# d104-lofi-delay.net
KiCad netlist of a schematic drawn in EAGLE
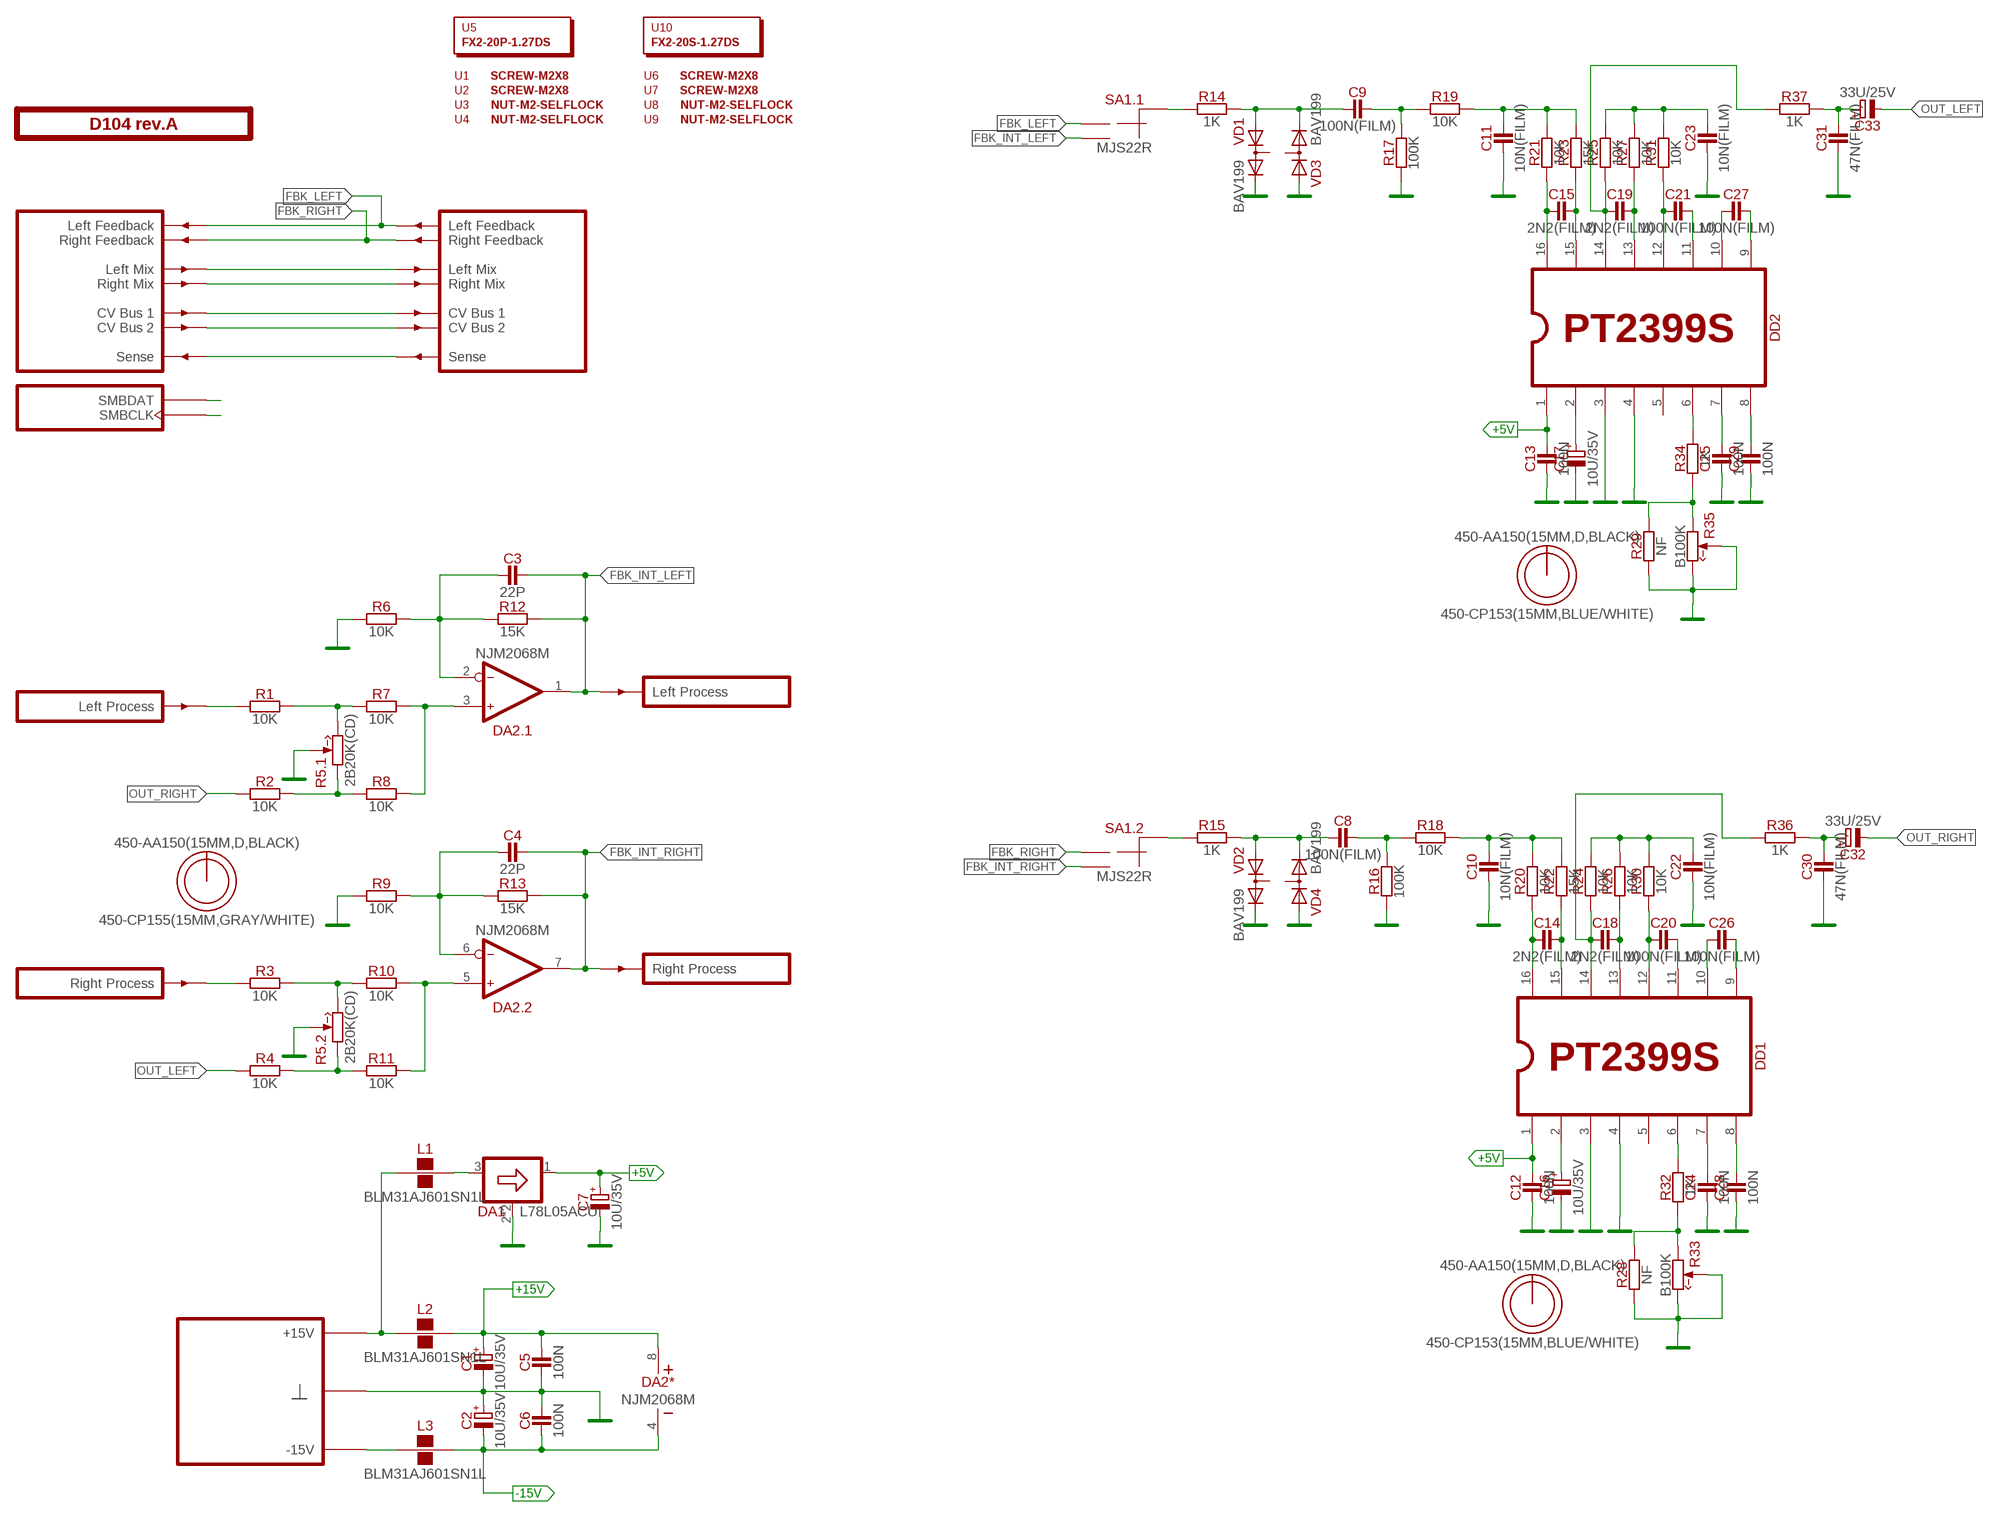
[diagram p0: schematic, sheet 1]

(export (version "E")
  (design (tool "Eeschema 10.0.6"))
  (components
    (comp (ref "C1")
      (value "10U/35V")
      (footprint "eagle-import:E2-5")
      (libsource (lib "eagle-import") (part "?10U/35V"))
    )
    (comp (ref "C2")
      (value "10U/35V")
      (footprint "eagle-import:E2-5")
      (libsource (lib "eagle-import") (part "?10U/35V"))
    )
    (comp (ref "C3")
      (value "22P")
      (footprint "eagle-import:C-0805")
      (libsource (lib "eagle-import") (part "?22P"))
    )
    (comp (ref "C4")
      (value "22P")
      (footprint "eagle-import:C-0805")
      (libsource (lib "eagle-import") (part "?22P"))
    )
    (comp (ref "C5")
      (value "100N")
      (footprint "eagle-import:C-0805")
      (libsource (lib "eagle-import") (part "?100N"))
    )
    (comp (ref "C6")
      (value "100N")
      (footprint "eagle-import:C-0805")
      (libsource (lib "eagle-import") (part "?100N"))
    )
    (comp (ref "C7")
      (value "10U/35V")
      (footprint "eagle-import:E2-5")
      (libsource (lib "eagle-import") (part "?10U/35V"))
    )
    (comp (ref "C8")
      (value "100N(FILM)")
      (footprint "eagle-import:C050-025X075")
      (libsource (lib "eagle-import") (part "?100N(FILM)"))
    )
    (comp (ref "C9")
      (value "100N(FILM)")
      (footprint "eagle-import:C050-025X075")
      (libsource (lib "eagle-import") (part "?100N(FILM)"))
    )
    (comp (ref "C10")
      (value "10N(FILM)")
      (footprint "eagle-import:C050-025X075")
      (libsource (lib "eagle-import") (part "?10N(FILM)"))
    )
    (comp (ref "C11")
      (value "10N(FILM)")
      (footprint "eagle-import:C050-025X075")
      (libsource (lib "eagle-import") (part "?10N(FILM)"))
    )
    (comp (ref "C12")
      (value "100N")
      (footprint "eagle-import:C-0805")
      (libsource (lib "eagle-import") (part "?100N"))
    )
    (comp (ref "C13")
      (value "100N")
      (footprint "eagle-import:C-0805")
      (libsource (lib "eagle-import") (part "?100N"))
    )
    (comp (ref "C14")
      (value "2N2(FILM)")
      (footprint "eagle-import:C050-025X075")
      (libsource (lib "eagle-import") (part "?2N2(FILM)"))
    )
    (comp (ref "C15")
      (value "2N2(FILM)")
      (footprint "eagle-import:C050-025X075")
      (libsource (lib "eagle-import") (part "?2N2(FILM)"))
    )
    (comp (ref "C16")
      (value "10U/35V")
      (footprint "eagle-import:E2-5")
      (libsource (lib "eagle-import") (part "?10U/35V"))
    )
    (comp (ref "C17")
      (value "10U/35V")
      (footprint "eagle-import:E2-5")
      (libsource (lib "eagle-import") (part "?10U/35V"))
    )
    (comp (ref "C18")
      (value "2N2(FILM)")
      (footprint "eagle-import:C050-025X075")
      (libsource (lib "eagle-import") (part "?2N2(FILM)"))
    )
    (comp (ref "C19")
      (value "2N2(FILM)")
      (footprint "eagle-import:C050-025X075")
      (libsource (lib "eagle-import") (part "?2N2(FILM)"))
    )
    (comp (ref "C20")
      (value "100N(FILM)")
      (footprint "eagle-import:C050-025X075")
      (libsource (lib "eagle-import") (part "?100N(FILM)"))
    )
    (comp (ref "C21")
      (value "100N(FILM)")
      (footprint "eagle-import:C050-025X075")
      (libsource (lib "eagle-import") (part "?100N(FILM)"))
    )
    (comp (ref "C22")
      (value "10N(FILM)")
      (footprint "eagle-import:C050-025X075")
      (libsource (lib "eagle-import") (part "?10N(FILM)"))
    )
    (comp (ref "C23")
      (value "10N(FILM)")
      (footprint "eagle-import:C050-025X075")
      (libsource (lib "eagle-import") (part "?10N(FILM)"))
    )
    (comp (ref "C24")
      (value "100N")
      (footprint "eagle-import:C-0805")
      (libsource (lib "eagle-import") (part "?100N"))
    )
    (comp (ref "C25")
      (value "100N")
      (footprint "eagle-import:C-0805")
      (libsource (lib "eagle-import") (part "?100N"))
    )
    (comp (ref "C26")
      (value "100N(FILM)")
      (footprint "eagle-import:C050-025X075")
      (libsource (lib "eagle-import") (part "?100N(FILM)"))
    )
    (comp (ref "C27")
      (value "100N(FILM)")
      (footprint "eagle-import:C050-025X075")
      (libsource (lib "eagle-import") (part "?100N(FILM)"))
    )
    (comp (ref "C28")
      (value "100N")
      (footprint "eagle-import:C-0805")
      (libsource (lib "eagle-import") (part "?100N"))
    )
    (comp (ref "C29")
      (value "100N")
      (footprint "eagle-import:C-0805")
      (libsource (lib "eagle-import") (part "?100N"))
    )
    (comp (ref "C30")
      (value "47N(FILM)")
      (footprint "eagle-import:C050-025X075")
      (libsource (lib "eagle-import") (part "?47N(FILM)"))
    )
    (comp (ref "C31")
      (value "47N(FILM)")
      (footprint "eagle-import:C050-025X075")
      (libsource (lib "eagle-import") (part "?47N(FILM)"))
    )
    (comp (ref "C32")
      (value "33U/25V")
      (footprint "eagle-import:E2,5-7")
      (libsource (lib "eagle-import") (part "?33U/25V"))
    )
    (comp (ref "C33")
      (value "33U/25V")
      (footprint "eagle-import:E2,5-7")
      (libsource (lib "eagle-import") (part "?33U/25V"))
    )
    (comp (ref "DA1")
      (value "L78L05ACU")
      (footprint "eagle-import:SOT89")
      (libsource (lib "eagle-import") (part "?L78L05ACU"))
    )
    (comp (ref "DA2")
      (value "NJM2068M")
      (footprint "eagle-import:SO-8")
      (libsource (lib "eagle-import") (part "NJM2068M"))
    )
    (comp (ref "DD1")
      (value "PT2399S")
      (footprint "eagle-import:SO-16")
      (libsource (lib "eagle-import") (part "PT2399S"))
    )
    (comp (ref "DD2")
      (value "PT2399S")
      (footprint "eagle-import:SO-16")
      (libsource (lib "eagle-import") (part "PT2399S"))
    )
    (comp (ref "L1")
      (value "BLM31AJ601SN1L")
      (footprint "eagle-import:1206")
      (libsource (lib "eagle-import") (part "BLM31AJ601SN1L"))
    )
    (comp (ref "L2")
      (value "BLM31AJ601SN1L")
      (footprint "eagle-import:1206")
      (libsource (lib "eagle-import") (part "BLM31AJ601SN1L"))
    )
    (comp (ref "L3")
      (value "BLM31AJ601SN1L")
      (footprint "eagle-import:1206")
      (libsource (lib "eagle-import") (part "BLM31AJ601SN1L"))
    )
    (comp (ref "O1")
      (value "450-AA150(15MM,D,BLACK)")
      (footprint "eagle-import:EMPTY")
      (libsource (lib "eagle-import") (part "450-AA?150(15MM,D,BLACK)"))
    )
    (comp (ref "O2")
      (value "450-CP155(15MM,GRAY/WHITE)")
      (footprint "eagle-import:EMPTY")
      (libsource (lib "eagle-import") (part "450-C?P155(15MM,GRAY/WHITE)"))
    )
    (comp (ref "O3")
      (value "450-AA150(15MM,D,BLACK)")
      (footprint "eagle-import:EMPTY")
      (libsource (lib "eagle-import") (part "450-AA?150(15MM,D,BLACK)"))
    )
    (comp (ref "O4")
      (value "450-CP153(15MM,BLUE/WHITE)")
      (footprint "eagle-import:EMPTY")
      (libsource (lib "eagle-import") (part "450-C?P153(15MM,BLUE/WHITE)"))
    )
    (comp (ref "O5")
      (value "450-AA150(15MM,D,BLACK)")
      (footprint "eagle-import:EMPTY")
      (libsource (lib "eagle-import") (part "450-AA?150(15MM,D,BLACK)"))
    )
    (comp (ref "O6")
      (value "450-CP153(15MM,BLUE/WHITE)")
      (footprint "eagle-import:EMPTY")
      (libsource (lib "eagle-import") (part "450-C?P153(15MM,BLUE/WHITE)"))
    )
    (comp (ref "PCB1")
      (value "D104 rev.A")
      (footprint "eagle-import:ST2-BOARD-50")
      (libsource (lib "eagle-import") (part "ST2-BOARD-?50"))
    )
    (comp (ref "R1")
      (value "10K")
      (footprint "eagle-import:R-0805")
      (libsource (lib "eagle-import") (part "?10K"))
    )
    (comp (ref "R2")
      (value "10K")
      (footprint "eagle-import:R-0805")
      (libsource (lib "eagle-import") (part "?10K"))
    )
    (comp (ref "R3")
      (value "10K")
      (footprint "eagle-import:R-0805")
      (libsource (lib "eagle-import") (part "?10K"))
    )
    (comp (ref "R4")
      (value "10K")
      (footprint "eagle-import:R-0805")
      (libsource (lib "eagle-import") (part "?10K"))
    )
    (comp (ref "R5")
      (value "2B20K(CD)")
      (footprint "eagle-import:RV11-DUAL")
      (libsource (lib "eagle-import") (part "2?B20K(CD)"))
    )
    (comp (ref "R6")
      (value "10K")
      (footprint "eagle-import:R-0805")
      (libsource (lib "eagle-import") (part "?10K"))
    )
    (comp (ref "R7")
      (value "10K")
      (footprint "eagle-import:R-0805")
      (libsource (lib "eagle-import") (part "?10K"))
    )
    (comp (ref "R8")
      (value "10K")
      (footprint "eagle-import:R-0805")
      (libsource (lib "eagle-import") (part "?10K"))
    )
    (comp (ref "R9")
      (value "10K")
      (footprint "eagle-import:R-0805")
      (libsource (lib "eagle-import") (part "?10K"))
    )
    (comp (ref "R10")
      (value "10K")
      (footprint "eagle-import:R-0805")
      (libsource (lib "eagle-import") (part "?10K"))
    )
    (comp (ref "R11")
      (value "10K")
      (footprint "eagle-import:R-0805")
      (libsource (lib "eagle-import") (part "?10K"))
    )
    (comp (ref "R12")
      (value "15K")
      (footprint "eagle-import:R-0805")
      (libsource (lib "eagle-import") (part "?15K"))
    )
    (comp (ref "R13")
      (value "15K")
      (footprint "eagle-import:R-0805")
      (libsource (lib "eagle-import") (part "?15K"))
    )
    (comp (ref "R14")
      (value "1K")
      (footprint "eagle-import:R-0805")
      (libsource (lib "eagle-import") (part "?1K"))
    )
    (comp (ref "R15")
      (value "1K")
      (footprint "eagle-import:R-0805")
      (libsource (lib "eagle-import") (part "?1K"))
    )
    (comp (ref "R16")
      (value "100K")
      (footprint "eagle-import:R-0805")
      (libsource (lib "eagle-import") (part "?100K"))
    )
    (comp (ref "R17")
      (value "100K")
      (footprint "eagle-import:R-0805")
      (libsource (lib "eagle-import") (part "?100K"))
    )
    (comp (ref "R18")
      (value "10K")
      (footprint "eagle-import:R-0805")
      (libsource (lib "eagle-import") (part "?10K"))
    )
    (comp (ref "R19")
      (value "10K")
      (footprint "eagle-import:R-0805")
      (libsource (lib "eagle-import") (part "?10K"))
    )
    (comp (ref "R20")
      (value "10K")
      (footprint "eagle-import:R-0805")
      (libsource (lib "eagle-import") (part "?10K"))
    )
    (comp (ref "R21")
      (value "10K")
      (footprint "eagle-import:R-0805")
      (libsource (lib "eagle-import") (part "?10K"))
    )
    (comp (ref "R22")
      (value "15K")
      (footprint "eagle-import:R-0805")
      (libsource (lib "eagle-import") (part "?15K"))
    )
    (comp (ref "R23")
      (value "15K")
      (footprint "eagle-import:R-0805")
      (libsource (lib "eagle-import") (part "?15K"))
    )
    (comp (ref "R24")
      (value "10K")
      (footprint "eagle-import:R-0805")
      (libsource (lib "eagle-import") (part "?10K"))
    )
    (comp (ref "R25")
      (value "10K")
      (footprint "eagle-import:R-0805")
      (libsource (lib "eagle-import") (part "?10K"))
    )
    (comp (ref "R26")
      (value "10K")
      (footprint "eagle-import:R-0805")
      (libsource (lib "eagle-import") (part "?10K"))
    )
    (comp (ref "R27")
      (value "10K")
      (footprint "eagle-import:R-0805")
      (libsource (lib "eagle-import") (part "?10K"))
    )
    (comp (ref "R28")
      (value "NF")
      (footprint "eagle-import:R-0805")
      (libsource (lib "eagle-import") (part "?NF"))
    )
    (comp (ref "R29")
      (value "NF")
      (footprint "eagle-import:R-0805")
      (libsource (lib "eagle-import") (part "?NF"))
    )
    (comp (ref "R30")
      (value "10K")
      (footprint "eagle-import:R-0805")
      (libsource (lib "eagle-import") (part "?10K"))
    )
    (comp (ref "R31")
      (value "10K")
      (footprint "eagle-import:R-0805")
      (libsource (lib "eagle-import") (part "?10K"))
    )
    (comp (ref "R32")
      (value "1K")
      (footprint "eagle-import:R-0805")
      (libsource (lib "eagle-import") (part "?1K"))
    )
    (comp (ref "R33")
      (value "B100K")
      (footprint "eagle-import:RV11-SINGLE")
      (libsource (lib "eagle-import") (part "?B100K"))
    )
    (comp (ref "R34")
      (value "1K")
      (footprint "eagle-import:R-0805")
      (libsource (lib "eagle-import") (part "?1K"))
    )
    (comp (ref "R35")
      (value "B100K")
      (footprint "eagle-import:RV11-SINGLE")
      (libsource (lib "eagle-import") (part "?B100K"))
    )
    (comp (ref "R36")
      (value "1K")
      (footprint "eagle-import:R-0805")
      (libsource (lib "eagle-import") (part "?1K"))
    )
    (comp (ref "R37")
      (value "1K")
      (footprint "eagle-import:R-0805")
      (libsource (lib "eagle-import") (part "?1K"))
    )
    (comp (ref "SA1")
      (value "MJS22R")
      (footprint "eagle-import:APEM-MJS22R")
      (libsource (lib "eagle-import") (part "MJS22R"))
    )
    (comp (ref "U1")
      (value "SCREW-M2X8")
      (footprint "eagle-import:EMPTY")
      (libsource (lib "eagle-import") (part "?SCREW-M2X8"))
    )
    (comp (ref "U2")
      (value "SCREW-M2X8")
      (footprint "eagle-import:EMPTY")
      (libsource (lib "eagle-import") (part "?SCREW-M2X8"))
    )
    (comp (ref "U3")
      (value "NUT-M2-SELFLOCK")
      (footprint "eagle-import:EMPTY")
      (libsource (lib "eagle-import") (part "?NUT-M2-SELFLOCK"))
    )
    (comp (ref "U4")
      (value "NUT-M2-SELFLOCK")
      (footprint "eagle-import:EMPTY")
      (libsource (lib "eagle-import") (part "?NUT-M2-SELFLOCK"))
    )
    (comp (ref "U5")
      (value "FX2-20P-1.27DS")
      (footprint "eagle-import:EMPTY")
      (libsource (lib "eagle-import") (part "?FX2-20P-1.27DS"))
    )
    (comp (ref "U6")
      (value "SCREW-M2X8")
      (footprint "eagle-import:EMPTY")
      (libsource (lib "eagle-import") (part "?SCREW-M2X8"))
    )
    (comp (ref "U7")
      (value "SCREW-M2X8")
      (footprint "eagle-import:EMPTY")
      (libsource (lib "eagle-import") (part "?SCREW-M2X8"))
    )
    (comp (ref "U8")
      (value "NUT-M2-SELFLOCK")
      (footprint "eagle-import:EMPTY")
      (libsource (lib "eagle-import") (part "?NUT-M2-SELFLOCK"))
    )
    (comp (ref "U9")
      (value "NUT-M2-SELFLOCK")
      (footprint "eagle-import:EMPTY")
      (libsource (lib "eagle-import") (part "?NUT-M2-SELFLOCK"))
    )
    (comp (ref "U10")
      (value "FX2-20S-1.27DS")
      (footprint "eagle-import:EMPTY")
      (libsource (lib "eagle-import") (part "?FX2-20S-1.27DS"))
    )
    (comp (ref "VD1")
      (value "BAV199")
      (footprint "eagle-import:SOT23")
      (libsource (lib "eagle-import") (part "BAV199"))
    )
    (comp (ref "VD2")
      (value "BAV199")
      (footprint "eagle-import:SOT23")
      (libsource (lib "eagle-import") (part "BAV199"))
    )
    (comp (ref "VD3")
      (value "BAV199")
      (footprint "eagle-import:SOT23")
      (libsource (lib "eagle-import") (part "BAV199"))
    )
    (comp (ref "VD4")
      (value "BAV199")
      (footprint "eagle-import:SOT23")
      (libsource (lib "eagle-import") (part "BAV199"))
    )
  )
  (nets
    (net (code "1") (name "+5V") (class "Default")
      (node (ref "C12") (pin "2") (pinfunction "2_2") (pintype "passive"))
      (node (ref "C13") (pin "2") (pinfunction "2_2") (pintype "passive"))
      (node (ref "C7") (pin "+") (pinfunction "+_+") (pintype "passive"))
      (node (ref "DA1") (pin "1") (pinfunction "OUT_1") (pintype "power_in"))
      (node (ref "DD1") (pin "1") (pinfunction "1_1") (pintype "bidirectional"))
      (node (ref "DD2") (pin "1") (pinfunction "1_1") (pintype "bidirectional"))
    )
    (net (code "2") (name "+15V") (class "Default")
      (node (ref "C1") (pin "+") (pinfunction "+_+") (pintype "passive"))
      (node (ref "C5") (pin "2") (pinfunction "2_2") (pintype "passive"))
      (node (ref "DA2") (pin "8") (pinfunction "V+_8") (pintype "power_in"))
      (node (ref "L2") (pin "2") (pinfunction "2_2") (pintype "passive"))
    )
    (net (code "3") (name "-15V") (class "Default")
      (node (ref "C2") (pin "-") (pinfunction "-_-") (pintype "passive"))
      (node (ref "C6") (pin "1") (pinfunction "1_1") (pintype "passive"))
      (node (ref "DA2") (pin "4") (pinfunction "V-_4") (pintype "power_in"))
      (node (ref "L3") (pin "2") (pinfunction "2_2") (pintype "passive"))
    )
    (net (code "4") (name "FBK_INT_LEFT") (class "Default")
      (node (ref "C3") (pin "2") (pinfunction "2_2") (pintype "passive"))
      (node (ref "DA2") (pin "1") (pinfunction "OUT_1") (pintype "output"))
      (node (ref "PCB1") (pin "BOUTL'") (pinfunction "OUTL_BOUTL'") (pintype "bidirectional"))
      (node (ref "R12") (pin "2") (pinfunction "2_2") (pintype "passive"))
      (node (ref "SA1") (pin "NO1") (pinfunction "2_NO1") (pintype "passive"))
    )
    (net (code "5") (name "FBK_INT_RIGHT") (class "Default")
      (node (ref "C4") (pin "2") (pinfunction "2_2") (pintype "passive"))
      (node (ref "DA2") (pin "7") (pinfunction "OUT_7") (pintype "output"))
      (node (ref "PCB1") (pin "BOUTR'") (pinfunction "OUTR_BOUTR'") (pintype "bidirectional"))
      (node (ref "R13") (pin "2") (pinfunction "2_2") (pintype "passive"))
      (node (ref "SA1") (pin "NO2") (pinfunction "2_NO2") (pintype "passive"))
    )
    (net (code "6") (name "FBK_LEFT") (class "Default")
      (node (ref "PCB1") (pin "ALFBK") (pinfunction "LFBK_ALFBK") (pintype "bidirectional"))
      (node (ref "PCB1") (pin "ALFBK'") (pinfunction "LFBK'_ALFBK'") (pintype "bidirectional"))
      (node (ref "SA1") (pin "NC1") (pinfunction "1_NC1") (pintype "passive"))
    )
    (net (code "7") (name "FBK_RIGHT") (class "Default")
      (node (ref "PCB1") (pin "ARFBK") (pinfunction "RFBK_ARFBK") (pintype "bidirectional"))
      (node (ref "PCB1") (pin "ARFBK'") (pinfunction "RFBK'_ARFBK'") (pintype "bidirectional"))
      (node (ref "SA1") (pin "NC2") (pinfunction "1_NC2") (pintype "passive"))
    )
    (net (code "8") (name "GND") (class "Default")
      (node (ref "C1") (pin "-") (pinfunction "-_-") (pintype "passive"))
      (node (ref "C10") (pin "1") (pinfunction "1_1") (pintype "passive"))
      (node (ref "C11") (pin "1") (pinfunction "1_1") (pintype "passive"))
      (node (ref "C12") (pin "1") (pinfunction "1_1") (pintype "passive"))
      (node (ref "C13") (pin "1") (pinfunction "1_1") (pintype "passive"))
      (node (ref "C16") (pin "-") (pinfunction "-_-") (pintype "passive"))
      (node (ref "C17") (pin "-") (pinfunction "-_-") (pintype "passive"))
      (node (ref "C2") (pin "+") (pinfunction "+_+") (pintype "passive"))
      (node (ref "C22") (pin "1") (pinfunction "1_1") (pintype "passive"))
      (node (ref "C23") (pin "1") (pinfunction "1_1") (pintype "passive"))
      (node (ref "C24") (pin "1") (pinfunction "1_1") (pintype "passive"))
      (node (ref "C25") (pin "1") (pinfunction "1_1") (pintype "passive"))
      (node (ref "C28") (pin "1") (pinfunction "1_1") (pintype "passive"))
      (node (ref "C29") (pin "1") (pinfunction "1_1") (pintype "passive"))
      (node (ref "C30") (pin "1") (pinfunction "1_1") (pintype "passive"))
      (node (ref "C31") (pin "1") (pinfunction "1_1") (pintype "passive"))
      (node (ref "C5") (pin "1") (pinfunction "1_1") (pintype "passive"))
      (node (ref "C6") (pin "2") (pinfunction "2_2") (pintype "passive"))
      (node (ref "C7") (pin "-") (pinfunction "-_-") (pintype "passive"))
      (node (ref "DA1") (pin "2") (pinfunction "GND_2") (pintype "power_in"))
      (node (ref "DA1") (pin "2@1") (pinfunction "GND_2@1") (pintype "power_in"))
      (node (ref "DD1") (pin "3") (pinfunction "3_3") (pintype "bidirectional"))
      (node (ref "DD1") (pin "4") (pinfunction "4_4") (pintype "bidirectional"))
      (node (ref "DD2") (pin "3") (pinfunction "3_3") (pintype "bidirectional"))
      (node (ref "DD2") (pin "4") (pinfunction "4_4") (pintype "bidirectional"))
      (node (ref "PCB1") (pin "B4") (pinfunction "GND_B4") (pintype "bidirectional"))
      (node (ref "PCB1") (pin "B4'") (pinfunction "GND_B4'") (pintype "bidirectional"))
      (node (ref "PCB1") (pin "B5") (pinfunction "GND_B5") (pintype "bidirectional"))
      (node (ref "PCB1") (pin "B5'") (pinfunction "GND_B5'") (pintype "bidirectional"))
      (node (ref "PCB1") (pin "B6") (pinfunction "GND_B6") (pintype "bidirectional"))
      (node (ref "PCB1") (pin "B6'") (pinfunction "GND_B6'") (pintype "bidirectional"))
      (node (ref "PCB1") (pin "B7") (pinfunction "GND_B7") (pintype "bidirectional"))
      (node (ref "PCB1") (pin "B7'") (pinfunction "GND_B7'") (pintype "bidirectional"))
      (node (ref "PCB1") (pin "B8") (pinfunction "GND_B8") (pintype "bidirectional"))
      (node (ref "PCB1") (pin "B8'") (pinfunction "GND_B8'") (pintype "bidirectional"))
      (node (ref "R16") (pin "1") (pinfunction "1_1") (pintype "passive"))
      (node (ref "R17") (pin "1") (pinfunction "1_1") (pintype "passive"))
      (node (ref "R28") (pin "1") (pinfunction "1_1") (pintype "passive"))
      (node (ref "R29") (pin "1") (pinfunction "1_1") (pintype "passive"))
      (node (ref "R33") (pin "2") (pinfunction "W_2") (pintype "passive"))
      (node (ref "R33") (pin "3") (pinfunction "CW_3") (pintype "passive"))
      (node (ref "R35") (pin "2") (pinfunction "W_2") (pintype "passive"))
      (node (ref "R35") (pin "3") (pinfunction "CW_3") (pintype "passive"))
      (node (ref "R5") (pin "2") (pinfunction "W_2") (pintype "passive"))
      (node (ref "R5") (pin "2'") (pinfunction "W_2'") (pintype "passive"))
      (node (ref "R6") (pin "1") (pinfunction "1_1") (pintype "passive"))
      (node (ref "R9") (pin "1") (pinfunction "1_1") (pintype "passive"))
      (node (ref "VD1") (pin "2") (pinfunction "C_2") (pintype "passive"))
      (node (ref "VD2") (pin "2") (pinfunction "C_2") (pintype "passive"))
      (node (ref "VD3") (pin "1") (pinfunction "A_1") (pintype "passive"))
      (node (ref "VD4") (pin "1") (pinfunction "A_1") (pintype "passive"))
    )
    (net (code "9") (name "Net-(C8-Pad2)") (class "Default")
      (node (ref "C8") (pin "2") (pinfunction "2_2") (pintype "passive"))
      (node (ref "R16") (pin "2") (pinfunction "2_2") (pintype "passive"))
      (node (ref "R18") (pin "1") (pinfunction "1_1") (pintype "passive"))
    )
    (net (code "10") (name "Net-(C9-Pad2)") (class "Default")
      (node (ref "C9") (pin "2") (pinfunction "2_2") (pintype "passive"))
      (node (ref "R17") (pin "2") (pinfunction "2_2") (pintype "passive"))
      (node (ref "R19") (pin "1") (pinfunction "1_1") (pintype "passive"))
    )
    (net (code "11") (name "Net-(C10-Pad2)") (class "Default")
      (node (ref "C10") (pin "2") (pinfunction "2_2") (pintype "passive"))
      (node (ref "R18") (pin "2") (pinfunction "2_2") (pintype "passive"))
      (node (ref "R20") (pin "2") (pinfunction "2_2") (pintype "passive"))
      (node (ref "R22") (pin "2") (pinfunction "2_2") (pintype "passive"))
    )
    (net (code "12") (name "Net-(C11-Pad2)") (class "Default")
      (node (ref "C11") (pin "2") (pinfunction "2_2") (pintype "passive"))
      (node (ref "R19") (pin "2") (pinfunction "2_2") (pintype "passive"))
      (node (ref "R21") (pin "2") (pinfunction "2_2") (pintype "passive"))
      (node (ref "R23") (pin "2") (pinfunction "2_2") (pintype "passive"))
    )
    (net (code "13") (name "Net-(C14-Pad1)") (class "Default")
      (node (ref "C14") (pin "1") (pinfunction "1_1") (pintype "passive"))
      (node (ref "DD1") (pin "16") (pinfunction "16_16") (pintype "bidirectional"))
      (node (ref "R20") (pin "1") (pinfunction "1_1") (pintype "passive"))
    )
    (net (code "14") (name "Net-(C14-Pad2)") (class "Default")
      (node (ref "C14") (pin "2") (pinfunction "2_2") (pintype "passive"))
      (node (ref "DD1") (pin "15") (pinfunction "15_15") (pintype "bidirectional"))
      (node (ref "R22") (pin "1") (pinfunction "1_1") (pintype "passive"))
    )
    (net (code "15") (name "Net-(C15-Pad1)") (class "Default")
      (node (ref "C15") (pin "1") (pinfunction "1_1") (pintype "passive"))
      (node (ref "DD2") (pin "16") (pinfunction "16_16") (pintype "bidirectional"))
      (node (ref "R21") (pin "1") (pinfunction "1_1") (pintype "passive"))
    )
    (net (code "16") (name "Net-(C15-Pad2)") (class "Default")
      (node (ref "C15") (pin "2") (pinfunction "2_2") (pintype "passive"))
      (node (ref "DD2") (pin "15") (pinfunction "15_15") (pintype "bidirectional"))
      (node (ref "R23") (pin "1") (pinfunction "1_1") (pintype "passive"))
    )
    (net (code "17") (name "Net-(C16-Pad+)") (class "Default")
      (node (ref "C16") (pin "+") (pinfunction "+_+") (pintype "passive"))
      (node (ref "DD1") (pin "2") (pinfunction "2_2") (pintype "bidirectional"))
    )
    (net (code "18") (name "Net-(C17-Pad+)") (class "Default")
      (node (ref "C17") (pin "+") (pinfunction "+_+") (pintype "passive"))
      (node (ref "DD2") (pin "2") (pinfunction "2_2") (pintype "bidirectional"))
    )
    (net (code "19") (name "Net-(C18-Pad1)") (class "Default")
      (node (ref "C18") (pin "1") (pinfunction "1_1") (pintype "passive"))
      (node (ref "DD1") (pin "14") (pinfunction "14_14") (pintype "bidirectional"))
      (node (ref "R24") (pin "1") (pinfunction "1_1") (pintype "passive"))
      (node (ref "R36") (pin "1") (pinfunction "1_1") (pintype "passive"))
    )
    (net (code "20") (name "Net-(C18-Pad2)") (class "Default")
      (node (ref "C18") (pin "2") (pinfunction "2_2") (pintype "passive"))
      (node (ref "DD1") (pin "13") (pinfunction "13_13") (pintype "bidirectional"))
      (node (ref "R26") (pin "1") (pinfunction "1_1") (pintype "passive"))
    )
    (net (code "21") (name "Net-(C19-Pad1)") (class "Default")
      (node (ref "C19") (pin "1") (pinfunction "1_1") (pintype "passive"))
      (node (ref "DD2") (pin "14") (pinfunction "14_14") (pintype "bidirectional"))
      (node (ref "R25") (pin "1") (pinfunction "1_1") (pintype "passive"))
      (node (ref "R37") (pin "1") (pinfunction "1_1") (pintype "passive"))
    )
    (net (code "22") (name "Net-(C19-Pad2)") (class "Default")
      (node (ref "C19") (pin "2") (pinfunction "2_2") (pintype "passive"))
      (node (ref "DD2") (pin "13") (pinfunction "13_13") (pintype "bidirectional"))
      (node (ref "R27") (pin "1") (pinfunction "1_1") (pintype "passive"))
    )
    (net (code "23") (name "Net-(C20-Pad1)") (class "Default")
      (node (ref "C20") (pin "1") (pinfunction "1_1") (pintype "passive"))
      (node (ref "DD1") (pin "12") (pinfunction "12_12") (pintype "bidirectional"))
      (node (ref "R30") (pin "1") (pinfunction "1_1") (pintype "passive"))
    )
    (net (code "24") (name "Net-(C20-Pad2)") (class "Default")
      (node (ref "C20") (pin "2") (pinfunction "2_2") (pintype "passive"))
      (node (ref "DD1") (pin "11") (pinfunction "11_11") (pintype "bidirectional"))
    )
    (net (code "25") (name "Net-(C21-Pad1)") (class "Default")
      (node (ref "C21") (pin "1") (pinfunction "1_1") (pintype "passive"))
      (node (ref "DD2") (pin "12") (pinfunction "12_12") (pintype "bidirectional"))
      (node (ref "R31") (pin "1") (pinfunction "1_1") (pintype "passive"))
    )
    (net (code "26") (name "Net-(C21-Pad2)") (class "Default")
      (node (ref "C21") (pin "2") (pinfunction "2_2") (pintype "passive"))
      (node (ref "DD2") (pin "11") (pinfunction "11_11") (pintype "bidirectional"))
    )
    (net (code "27") (name "Net-(C22-Pad2)") (class "Default")
      (node (ref "C22") (pin "2") (pinfunction "2_2") (pintype "passive"))
      (node (ref "R24") (pin "2") (pinfunction "2_2") (pintype "passive"))
      (node (ref "R26") (pin "2") (pinfunction "2_2") (pintype "passive"))
      (node (ref "R30") (pin "2") (pinfunction "2_2") (pintype "passive"))
    )
    (net (code "28") (name "Net-(C23-Pad2)") (class "Default")
      (node (ref "C23") (pin "2") (pinfunction "2_2") (pintype "passive"))
      (node (ref "R25") (pin "2") (pinfunction "2_2") (pintype "passive"))
      (node (ref "R27") (pin "2") (pinfunction "2_2") (pintype "passive"))
      (node (ref "R31") (pin "2") (pinfunction "2_2") (pintype "passive"))
    )
    (net (code "29") (name "Net-(C24-Pad2)") (class "Default")
      (node (ref "C24") (pin "2") (pinfunction "2_2") (pintype "passive"))
      (node (ref "DD1") (pin "7") (pinfunction "7_7") (pintype "bidirectional"))
    )
    (net (code "30") (name "Net-(C25-Pad2)") (class "Default")
      (node (ref "C25") (pin "2") (pinfunction "2_2") (pintype "passive"))
      (node (ref "DD2") (pin "7") (pinfunction "7_7") (pintype "bidirectional"))
    )
    (net (code "31") (name "Net-(C26-Pad1)") (class "Default")
      (node (ref "C26") (pin "1") (pinfunction "1_1") (pintype "passive"))
      (node (ref "DD1") (pin "10") (pinfunction "10_10") (pintype "bidirectional"))
    )
    (net (code "32") (name "Net-(C26-Pad2)") (class "Default")
      (node (ref "C26") (pin "2") (pinfunction "2_2") (pintype "passive"))
      (node (ref "DD1") (pin "9") (pinfunction "9_9") (pintype "bidirectional"))
    )
    (net (code "33") (name "Net-(C27-Pad1)") (class "Default")
      (node (ref "C27") (pin "1") (pinfunction "1_1") (pintype "passive"))
      (node (ref "DD2") (pin "10") (pinfunction "10_10") (pintype "bidirectional"))
    )
    (net (code "34") (name "Net-(C27-Pad2)") (class "Default")
      (node (ref "C27") (pin "2") (pinfunction "2_2") (pintype "passive"))
      (node (ref "DD2") (pin "9") (pinfunction "9_9") (pintype "bidirectional"))
    )
    (net (code "35") (name "Net-(C28-Pad2)") (class "Default")
      (node (ref "C28") (pin "2") (pinfunction "2_2") (pintype "passive"))
      (node (ref "DD1") (pin "8") (pinfunction "8_8") (pintype "bidirectional"))
    )
    (net (code "36") (name "Net-(C29-Pad2)") (class "Default")
      (node (ref "C29") (pin "2") (pinfunction "2_2") (pintype "passive"))
      (node (ref "DD2") (pin "8") (pinfunction "8_8") (pintype "bidirectional"))
    )
    (net (code "37") (name "Net-(C30-Pad2)") (class "Default")
      (node (ref "C30") (pin "2") (pinfunction "2_2") (pintype "passive"))
      (node (ref "C32") (pin "+") (pinfunction "+_+") (pintype "passive"))
      (node (ref "R36") (pin "2") (pinfunction "2_2") (pintype "passive"))
    )
    (net (code "38") (name "Net-(C31-Pad2)") (class "Default")
      (node (ref "C31") (pin "2") (pinfunction "2_2") (pintype "passive"))
      (node (ref "C33") (pin "+") (pinfunction "+_+") (pintype "passive"))
      (node (ref "R37") (pin "2") (pinfunction "2_2") (pintype "passive"))
    )
    (net (code "39") (name "Net-(DA1-IN)") (class "Default")
      (node (ref "DA1") (pin "3") (pinfunction "IN_3") (pintype "power_in"))
      (node (ref "L1") (pin "2") (pinfunction "2_2") (pintype "passive"))
    )
    (net (code "40") (name "Net-(DA2B-IN+)") (class "Default")
      (node (ref "DA2") (pin "3") (pinfunction "IN+_3") (pintype "input"))
      (node (ref "R7") (pin "2") (pinfunction "2_2") (pintype "passive"))
      (node (ref "R8") (pin "2") (pinfunction "2_2") (pintype "passive"))
    )
    (net (code "41") (name "Net-(DA2B-IN-)") (class "Default")
      (node (ref "C3") (pin "1") (pinfunction "1_1") (pintype "passive"))
      (node (ref "DA2") (pin "2") (pinfunction "IN-_2") (pintype "input"))
      (node (ref "R12") (pin "1") (pinfunction "1_1") (pintype "passive"))
      (node (ref "R6") (pin "2") (pinfunction "2_2") (pintype "passive"))
    )
    (net (code "42") (name "Net-(DA2C-IN+)") (class "Default")
      (node (ref "DA2") (pin "5") (pinfunction "IN+_5") (pintype "input"))
      (node (ref "R10") (pin "2") (pinfunction "2_2") (pintype "passive"))
      (node (ref "R11") (pin "2") (pinfunction "2_2") (pintype "passive"))
    )
    (net (code "43") (name "Net-(DA2C-IN-)") (class "Default")
      (node (ref "C4") (pin "1") (pinfunction "1_1") (pintype "passive"))
      (node (ref "DA2") (pin "6") (pinfunction "IN-_6") (pintype "input"))
      (node (ref "R13") (pin "1") (pinfunction "1_1") (pintype "passive"))
      (node (ref "R9") (pin "2") (pinfunction "2_2") (pintype "passive"))
    )
    (net (code "44") (name "Net-(DD1-Pad6)") (class "Default")
      (node (ref "DD1") (pin "6") (pinfunction "6_6") (pintype "bidirectional"))
      (node (ref "R32") (pin "2") (pinfunction "2_2") (pintype "passive"))
    )
    (net (code "45") (name "Net-(DD2-Pad6)") (class "Default")
      (node (ref "DD2") (pin "6") (pinfunction "6_6") (pintype "bidirectional"))
      (node (ref "R34") (pin "2") (pinfunction "2_2") (pintype "passive"))
    )
    (net (code "46") (name "Net-(L1-Pad1)") (class "Default")
      (node (ref "L1") (pin "1") (pinfunction "1_1") (pintype "passive"))
      (node (ref "L2") (pin "1") (pinfunction "1_1") (pintype "passive"))
      (node (ref "PCB1") (pin "A+15") (pinfunction "P+15V_A+15") (pintype "bidirectional"))
      (node (ref "PCB1") (pin "A+15'") (pinfunction "P+15V_A+15'") (pintype "bidirectional"))
      (node (ref "PCB1") (pin "B+15") (pinfunction "P+15V_B+15") (pintype "bidirectional"))
      (node (ref "PCB1") (pin "B+15'") (pinfunction "P+15V_B+15'") (pintype "bidirectional"))
    )
    (net (code "47") (name "Net-(L3-Pad1)") (class "Default")
      (node (ref "L3") (pin "1") (pinfunction "1_1") (pintype "passive"))
      (node (ref "PCB1") (pin "A-15") (pinfunction "P-15V_A-15") (pintype "bidirectional"))
      (node (ref "PCB1") (pin "A-15'") (pinfunction "P-15V_A-15'") (pintype "bidirectional"))
      (node (ref "PCB1") (pin "B-15") (pinfunction "P-15V_B-15") (pintype "bidirectional"))
      (node (ref "PCB1") (pin "B-15'") (pinfunction "P-15V_B-15'") (pintype "bidirectional"))
    )
    (net (code "48") (name "Net-(PCB1B-INL)") (class "Default")
      (node (ref "PCB1") (pin "BINL") (pinfunction "INL_BINL") (pintype "bidirectional"))
      (node (ref "R1") (pin "1") (pinfunction "1_1") (pintype "passive"))
    )
    (net (code "49") (name "Net-(PCB1C-INR)") (class "Default")
      (node (ref "PCB1") (pin "BINR") (pinfunction "INR_BINR") (pintype "bidirectional"))
      (node (ref "R3") (pin "1") (pinfunction "1_1") (pintype "passive"))
    )
    (net (code "50") (name "Net-(PCB1F-CV1)") (class "Default")
      (node (ref "PCB1") (pin "ACV1") (pinfunction "CV1_ACV1") (pintype "bidirectional"))
      (node (ref "PCB1") (pin "ACV1'") (pinfunction "CV1'_ACV1'") (pintype "bidirectional"))
    )
    (net (code "51") (name "Net-(PCB1F-CV2)") (class "Default")
      (node (ref "PCB1") (pin "ACV2") (pinfunction "CV2_ACV2") (pintype "bidirectional"))
      (node (ref "PCB1") (pin "ACV2'") (pinfunction "CV2'_ACV2'") (pintype "bidirectional"))
    )
    (net (code "52") (name "Net-(PCB1F-LMIX)") (class "Default")
      (node (ref "PCB1") (pin "ALMIX") (pinfunction "LMIX_ALMIX") (pintype "bidirectional"))
      (node (ref "PCB1") (pin "ALMIX'") (pinfunction "LMIX'_ALMIX'") (pintype "bidirectional"))
    )
    (net (code "53") (name "Net-(PCB1F-RMIX)") (class "Default")
      (node (ref "PCB1") (pin "ARMIX") (pinfunction "RMIX_ARMIX") (pintype "bidirectional"))
      (node (ref "PCB1") (pin "ARMIX'") (pinfunction "RMIX'_ARMIX'") (pintype "bidirectional"))
    )
    (net (code "54") (name "Net-(PCB1F-SENSE)") (class "Default")
      (node (ref "PCB1") (pin "BSENSE") (pinfunction "SENSE_BSENSE") (pintype "bidirectional"))
      (node (ref "PCB1") (pin "BSENSE'") (pinfunction "SENSE'_BSENSE'") (pintype "bidirectional"))
    )
    (net (code "55") (name "Net-(PCB1H-SMBCLK-PadASMBCLK')") (class "Default")
      (node (ref "PCB1") (pin "ASMBCLK") (pinfunction "SMBCLK_ASMBCLK") (pintype "bidirectional"))
      (node (ref "PCB1") (pin "ASMBCLK'") (pinfunction "SMBCLK_ASMBCLK'") (pintype "bidirectional"))
    )
    (net (code "56") (name "Net-(PCB1H-SMBDAT-PadASMBDAT')") (class "Default")
      (node (ref "PCB1") (pin "ASMBDAT") (pinfunction "SMBDAT_ASMBDAT") (pintype "bidirectional"))
      (node (ref "PCB1") (pin "ASMBDAT'") (pinfunction "SMBDAT_ASMBDAT'") (pintype "bidirectional"))
    )
    (net (code "57") (name "Net-(R5A-CCW)") (class "Default")
      (node (ref "R2") (pin "2") (pinfunction "2_2") (pintype "passive"))
      (node (ref "R5") (pin "1") (pinfunction "CCW_1") (pintype "passive"))
      (node (ref "R8") (pin "1") (pinfunction "1_1") (pintype "passive"))
    )
    (net (code "58") (name "Net-(R5A-CW)") (class "Default")
      (node (ref "R1") (pin "2") (pinfunction "2_2") (pintype "passive"))
      (node (ref "R5") (pin "3") (pinfunction "CW_3") (pintype "passive"))
      (node (ref "R7") (pin "1") (pinfunction "1_1") (pintype "passive"))
    )
    (net (code "59") (name "Net-(R5B-CCW)") (class "Default")
      (node (ref "R11") (pin "1") (pinfunction "1_1") (pintype "passive"))
      (node (ref "R4") (pin "2") (pinfunction "2_2") (pintype "passive"))
      (node (ref "R5") (pin "1'") (pinfunction "CCW_1'") (pintype "passive"))
    )
    (net (code "60") (name "Net-(R5B-CW)") (class "Default")
      (node (ref "R10") (pin "1") (pinfunction "1_1") (pintype "passive"))
      (node (ref "R3") (pin "2") (pinfunction "2_2") (pintype "passive"))
      (node (ref "R5") (pin "3'") (pinfunction "CW_3'") (pintype "passive"))
    )
    (net (code "61") (name "Net-(R33-CCW)") (class "Default")
      (node (ref "R28") (pin "2") (pinfunction "2_2") (pintype "passive"))
      (node (ref "R32") (pin "1") (pinfunction "1_1") (pintype "passive"))
      (node (ref "R33") (pin "1") (pinfunction "CCW_1") (pintype "passive"))
    )
    (net (code "62") (name "Net-(R35-CCW)") (class "Default")
      (node (ref "R29") (pin "2") (pinfunction "2_2") (pintype "passive"))
      (node (ref "R34") (pin "1") (pinfunction "1_1") (pintype "passive"))
      (node (ref "R35") (pin "1") (pinfunction "CCW_1") (pintype "passive"))
    )
    (net (code "63") (name "Net-(SA1A-CM)") (class "Default")
      (node (ref "R14") (pin "1") (pinfunction "1_1") (pintype "passive"))
      (node (ref "SA1") (pin "C1") (pinfunction "CM_C1") (pintype "passive"))
    )
    (net (code "64") (name "Net-(SA1B-CM)") (class "Default")
      (node (ref "R15") (pin "1") (pinfunction "1_1") (pintype "passive"))
      (node (ref "SA1") (pin "C2") (pinfunction "CM_C2") (pintype "passive"))
    )
    (net (code "65") (name "Net-(VD1-A)") (class "Default")
      (node (ref "C9") (pin "1") (pinfunction "1_1") (pintype "passive"))
      (node (ref "R14") (pin "2") (pinfunction "2_2") (pintype "passive"))
      (node (ref "VD1") (pin "1") (pinfunction "A_1") (pintype "passive"))
      (node (ref "VD3") (pin "2") (pinfunction "C_2") (pintype "passive"))
    )
    (net (code "66") (name "Net-(VD2-A)") (class "Default")
      (node (ref "C8") (pin "1") (pinfunction "1_1") (pintype "passive"))
      (node (ref "R15") (pin "2") (pinfunction "2_2") (pintype "passive"))
      (node (ref "VD2") (pin "1") (pinfunction "A_1") (pintype "passive"))
      (node (ref "VD4") (pin "2") (pinfunction "C_2") (pintype "passive"))
    )
    (net (code "67") (name "OUT_LEFT") (class "Default")
      (node (ref "C33") (pin "-") (pinfunction "-_-") (pintype "passive"))
      (node (ref "R4") (pin "1") (pinfunction "1_1") (pintype "passive"))
    )
    (net (code "68") (name "OUT_RIGHT") (class "Default")
      (node (ref "C32") (pin "-") (pinfunction "-_-") (pintype "passive"))
      (node (ref "R2") (pin "1") (pinfunction "1_1") (pintype "passive"))
    )
    (net (code "69") (name "unconnected-(DD1-Pad5)") (class "Default")
      (node (ref "DD1") (pin "5") (pinfunction "5_5") (pintype "bidirectional"))
    )
    (net (code "70") (name "unconnected-(DD2-Pad5)") (class "Default")
      (node (ref "DD2") (pin "5") (pinfunction "5_5") (pintype "bidirectional"))
    )
    (net (code "71") (name "unconnected-(VD1-CMN-Pad3)") (class "Default")
      (node (ref "VD1") (pin "3") (pinfunction "CMN_3") (pintype "passive"))
    )
    (net (code "72") (name "unconnected-(VD2-CMN-Pad3)") (class "Default")
      (node (ref "VD2") (pin "3") (pinfunction "CMN_3") (pintype "passive"))
    )
    (net (code "73") (name "unconnected-(VD3-CMN-Pad3)") (class "Default")
      (node (ref "VD3") (pin "3") (pinfunction "CMN_3") (pintype "passive"))
    )
    (net (code "74") (name "unconnected-(VD4-CMN-Pad3)") (class "Default")
      (node (ref "VD4") (pin "3") (pinfunction "CMN_3") (pintype "passive"))
    )
  )
)
